# Glareshield-revA.net
KiCad netlist of a schematic drawn in EAGLE
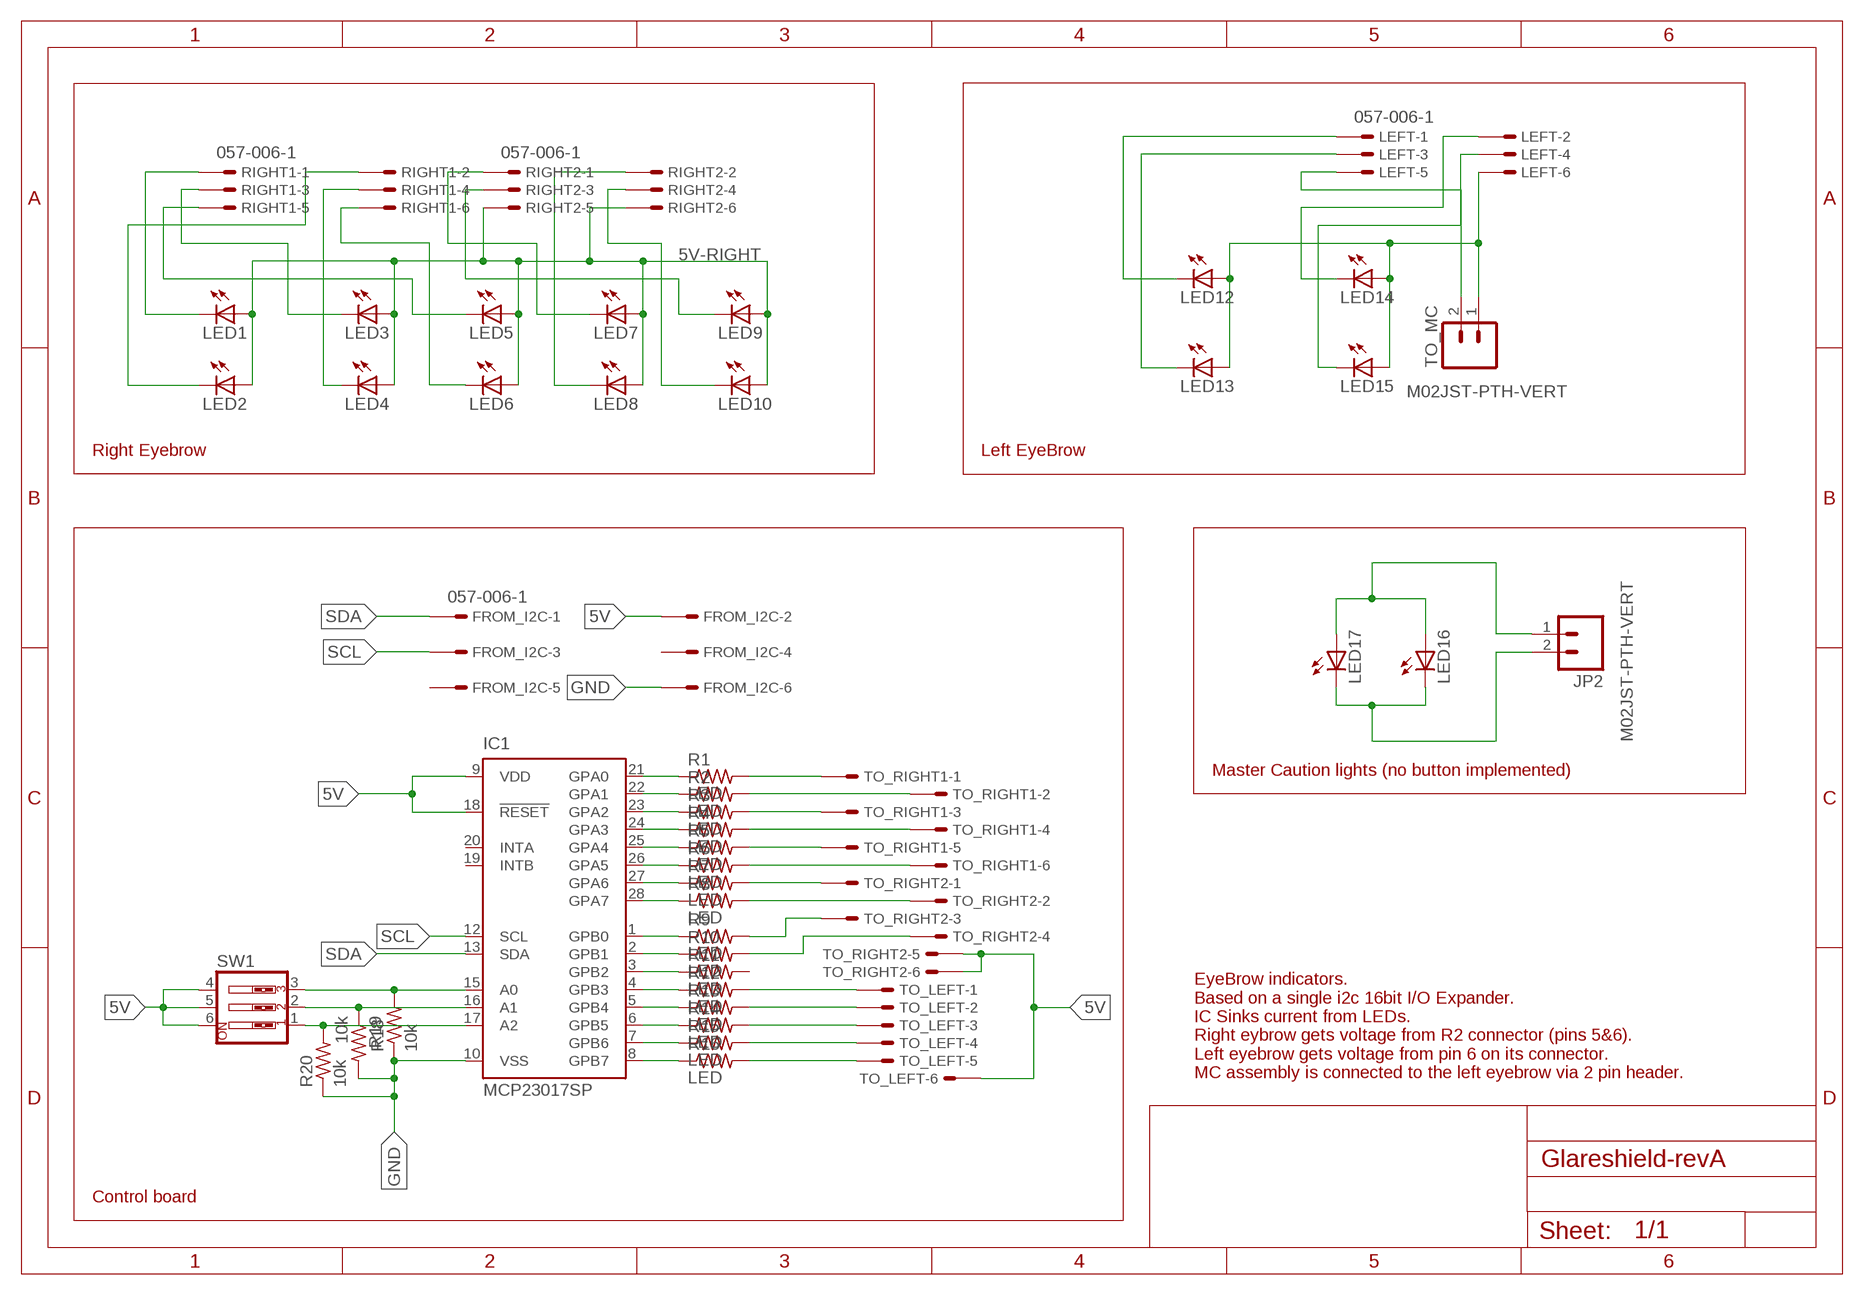
[diagram p0: schematic, sheet 1]

(export (version "E")
  (design (tool "Eeschema 10.0.6"))
  (components
    (comp (ref "FROM_I2C")
      (value "057-006-1")
      (footprint "eagle-import:057-006-1")
      (libsource (lib "eagle-import") (part "057-006-1"))
    )
    (comp (ref "IC1")
      (value "MCP23017SP")
      (footprint "eagle-import:DIL28-3")
      (fields (field (name "MF") "MICROCHIP") (field (name "MPN") "MCP23017-E/SP"))
      (libsource (lib "eagle-import") (part "MCP23017SP"))
    )
    (comp (ref "JP2")
      (value "M02JST-PTH-VERT")
      (footprint "eagle-import:JST-2-PTH-VERT")
      (libsource (lib "eagle-import") (part "M02JST-PTH-VERT"))
    )
    (comp (ref "LED1")
      (value "LED3MM")
      (footprint "eagle-import:LED3MM")
      (libsource (lib "eagle-import") (part "LED3MM"))
    )
    (comp (ref "LED2")
      (value "LED3MM")
      (footprint "eagle-import:LED3MM")
      (libsource (lib "eagle-import") (part "LED3MM"))
    )
    (comp (ref "LED3")
      (value "LED3MM")
      (footprint "eagle-import:LED3MM")
      (libsource (lib "eagle-import") (part "LED3MM"))
    )
    (comp (ref "LED4")
      (value "LED3MM")
      (footprint "eagle-import:LED3MM")
      (libsource (lib "eagle-import") (part "LED3MM"))
    )
    (comp (ref "LED5")
      (value "LED3MM")
      (footprint "eagle-import:LED3MM")
      (libsource (lib "eagle-import") (part "LED3MM"))
    )
    (comp (ref "LED6")
      (value "LED3MM")
      (footprint "eagle-import:LED3MM")
      (libsource (lib "eagle-import") (part "LED3MM"))
    )
    (comp (ref "LED7")
      (value "LED3MM")
      (footprint "eagle-import:LED3MM")
      (libsource (lib "eagle-import") (part "LED3MM"))
    )
    (comp (ref "LED8")
      (value "LED3MM")
      (footprint "eagle-import:LED3MM")
      (libsource (lib "eagle-import") (part "LED3MM"))
    )
    (comp (ref "LED9")
      (value "LED3MM")
      (footprint "eagle-import:LED3MM")
      (libsource (lib "eagle-import") (part "LED3MM"))
    )
    (comp (ref "LED10")
      (value "LED3MM")
      (footprint "eagle-import:LED3MM")
      (libsource (lib "eagle-import") (part "LED3MM"))
    )
    (comp (ref "LED12")
      (value "LED3MM")
      (footprint "eagle-import:LED3MM")
      (libsource (lib "eagle-import") (part "LED3MM"))
    )
    (comp (ref "LED13")
      (value "LED3MM")
      (footprint "eagle-import:LED3MM")
      (libsource (lib "eagle-import") (part "LED3MM"))
    )
    (comp (ref "LED14")
      (value "LED3MM")
      (footprint "eagle-import:LED3MM")
      (libsource (lib "eagle-import") (part "LED3MM"))
    )
    (comp (ref "LED15")
      (value "LED3MM")
      (footprint "eagle-import:LED3MM")
      (libsource (lib "eagle-import") (part "LED3MM"))
    )
    (comp (ref "LED16")
      (value "LED3MM")
      (footprint "eagle-import:LED3MM")
      (libsource (lib "eagle-import") (part "LED3MM"))
    )
    (comp (ref "LED17")
      (value "LED3MM")
      (footprint "eagle-import:LED3MM")
      (libsource (lib "eagle-import") (part "LED3MM"))
    )
    (comp (ref "LEFT")
      (value "057-006-1")
      (footprint "eagle-import:057-006-1")
      (libsource (lib "eagle-import") (part "057-006-1"))
    )
    (comp (ref "R1")
      (value "LED")
      (footprint "eagle-import:0204_7")
      (libsource (lib "eagle-import") (part "R-US_0204/7"))
    )
    (comp (ref "R2")
      (value "LED")
      (footprint "eagle-import:0204_7")
      (libsource (lib "eagle-import") (part "R-US_0204/7"))
    )
    (comp (ref "R3")
      (value "LED")
      (footprint "eagle-import:0204_7")
      (libsource (lib "eagle-import") (part "R-US_0204/7"))
    )
    (comp (ref "R4")
      (value "LED")
      (footprint "eagle-import:0204_7")
      (libsource (lib "eagle-import") (part "R-US_0204/7"))
    )
    (comp (ref "R5")
      (value "LED")
      (footprint "eagle-import:0204_7")
      (libsource (lib "eagle-import") (part "R-US_0204/7"))
    )
    (comp (ref "R6")
      (value "LED")
      (footprint "eagle-import:0204_7")
      (libsource (lib "eagle-import") (part "R-US_0204/7"))
    )
    (comp (ref "R7")
      (value "LED")
      (footprint "eagle-import:0204_7")
      (libsource (lib "eagle-import") (part "R-US_0204/7"))
    )
    (comp (ref "R8")
      (value "LED")
      (footprint "eagle-import:0204_7")
      (libsource (lib "eagle-import") (part "R-US_0204/7"))
    )
    (comp (ref "R9")
      (value "LED")
      (footprint "eagle-import:0204_7")
      (libsource (lib "eagle-import") (part "R-US_0204/7"))
    )
    (comp (ref "R10")
      (value "LED")
      (footprint "eagle-import:0204_7")
      (libsource (lib "eagle-import") (part "R-US_0204/7"))
    )
    (comp (ref "R11")
      (value "LED")
      (footprint "eagle-import:0204_7")
      (libsource (lib "eagle-import") (part "R-US_0204/7"))
    )
    (comp (ref "R12")
      (value "LED")
      (footprint "eagle-import:0204_7")
      (libsource (lib "eagle-import") (part "R-US_0204/7"))
    )
    (comp (ref "R13")
      (value "LED")
      (footprint "eagle-import:0204_7")
      (libsource (lib "eagle-import") (part "R-US_0204/7"))
    )
    (comp (ref "R14")
      (value "LED")
      (footprint "eagle-import:0204_7")
      (libsource (lib "eagle-import") (part "R-US_0204/7"))
    )
    (comp (ref "R15")
      (value "LED")
      (footprint "eagle-import:0204_7")
      (libsource (lib "eagle-import") (part "R-US_0204/7"))
    )
    (comp (ref "R16")
      (value "LED")
      (footprint "eagle-import:0204_7")
      (libsource (lib "eagle-import") (part "R-US_0204/7"))
    )
    (comp (ref "R18")
      (value "10k")
      (footprint "eagle-import:0204_7")
      (libsource (lib "eagle-import") (part "R-US_0204/7"))
    )
    (comp (ref "R19")
      (value "10k")
      (footprint "eagle-import:0204_7")
      (libsource (lib "eagle-import") (part "R-US_0204/7"))
    )
    (comp (ref "R20")
      (value "10k")
      (footprint "eagle-import:0204_7")
      (libsource (lib "eagle-import") (part "R-US_0204/7"))
    )
    (comp (ref "RIGHT1")
      (value "057-006-1")
      (footprint "eagle-import:057-006-1")
      (libsource (lib "eagle-import") (part "057-006-1"))
    )
    (comp (ref "RIGHT2")
      (value "057-006-1")
      (footprint "eagle-import:057-006-1")
      (libsource (lib "eagle-import") (part "057-006-1"))
    )
    (comp (ref "SW1")
      (value "SW_DIP-3")
      (footprint "eagle-import:EDG-03")
      (libsource (lib "eagle-import") (part "SW_DIP-3"))
    )
    (comp (ref "TO_LEFT")
      (value "057-006-1")
      (footprint "eagle-import:057-006-1")
      (libsource (lib "eagle-import") (part "057-006-1"))
    )
    (comp (ref "TO_MC")
      (value "M02JST-PTH-VERT")
      (footprint "eagle-import:JST-2-PTH-VERT")
      (libsource (lib "eagle-import") (part "M02JST-PTH-VERT"))
    )
    (comp (ref "TO_RIGHT1")
      (value "057-006-1")
      (footprint "eagle-import:057-006-1")
      (libsource (lib "eagle-import") (part "057-006-1"))
    )
    (comp (ref "TO_RIGHT2")
      (value "057-006-1")
      (footprint "eagle-import:057-006-1")
      (libsource (lib "eagle-import") (part "057-006-1"))
    )
  )
  (nets
    (net (code "1") (name "/5V-RIGHT") (class "Default")
      (node (ref "LED1") (pin "A") (pinfunction "A_A") (pintype "passive"))
      (node (ref "LED10") (pin "A") (pinfunction "A_A") (pintype "passive"))
      (node (ref "LED2") (pin "A") (pinfunction "A_A") (pintype "passive"))
      (node (ref "LED3") (pin "A") (pinfunction "A_A") (pintype "passive"))
      (node (ref "LED4") (pin "A") (pinfunction "A_A") (pintype "passive"))
      (node (ref "LED5") (pin "A") (pinfunction "A_A") (pintype "passive"))
      (node (ref "LED6") (pin "A") (pinfunction "A_A") (pintype "passive"))
      (node (ref "LED7") (pin "A") (pinfunction "A_A") (pintype "passive"))
      (node (ref "LED8") (pin "A") (pinfunction "A_A") (pintype "passive"))
      (node (ref "LED9") (pin "A") (pinfunction "A_A") (pintype "passive"))
      (node (ref "RIGHT2") (pin "5") (pinfunction "S_5") (pintype "passive"))
      (node (ref "RIGHT2") (pin "6") (pinfunction "S_6") (pintype "passive"))
    )
    (net (code "2") (name "5V") (class "Default")
      (node (ref "FROM_I2C") (pin "2") (pinfunction "S_2") (pintype "passive"))
      (node (ref "IC1") (pin "18") (pinfunction "~{RESET}_18") (pintype "input"))
      (node (ref "IC1") (pin "9") (pinfunction "VDD_9") (pintype "power_in"))
      (node (ref "SW1") (pin "4") (pinfunction "4_4") (pintype "passive"))
      (node (ref "SW1") (pin "5") (pinfunction "5_5") (pintype "passive"))
      (node (ref "SW1") (pin "6") (pinfunction "6_6") (pintype "passive"))
      (node (ref "TO_LEFT") (pin "6") (pinfunction "S_6") (pintype "passive"))
      (node (ref "TO_RIGHT2") (pin "5") (pinfunction "S_5") (pintype "passive"))
      (node (ref "TO_RIGHT2") (pin "6") (pinfunction "S_6") (pintype "passive"))
    )
    (net (code "3") (name "GND") (class "Default")
      (node (ref "FROM_I2C") (pin "6") (pinfunction "S_6") (pintype "passive"))
      (node (ref "IC1") (pin "10") (pinfunction "VSS_10") (pintype "power_in"))
      (node (ref "R18") (pin "1") (pinfunction "1_1") (pintype "passive"))
      (node (ref "R19") (pin "2") (pinfunction "2_2") (pintype "passive"))
      (node (ref "R20") (pin "1") (pinfunction "1_1") (pintype "passive"))
    )
    (net (code "4") (name "Net-(IC1-A0)") (class "Default")
      (node (ref "IC1") (pin "15") (pinfunction "A0_15") (pintype "input"))
      (node (ref "R18") (pin "2") (pinfunction "2_2") (pintype "passive"))
      (node (ref "SW1") (pin "3") (pinfunction "3_3") (pintype "passive"))
    )
    (net (code "5") (name "Net-(IC1-A1)") (class "Default")
      (node (ref "IC1") (pin "16") (pinfunction "A1_16") (pintype "input"))
      (node (ref "R19") (pin "1") (pinfunction "1_1") (pintype "passive"))
      (node (ref "SW1") (pin "2") (pinfunction "2_2") (pintype "passive"))
    )
    (net (code "6") (name "Net-(IC1-A2)") (class "Default")
      (node (ref "IC1") (pin "17") (pinfunction "A2_17") (pintype "input"))
      (node (ref "R20") (pin "2") (pinfunction "2_2") (pintype "passive"))
      (node (ref "SW1") (pin "1") (pinfunction "1_1") (pintype "passive"))
    )
    (net (code "7") (name "Net-(IC1-GPA0)") (class "Default")
      (node (ref "IC1") (pin "21") (pinfunction "GPA0_21") (pintype "bidirectional"))
      (node (ref "R1") (pin "1") (pinfunction "1_1") (pintype "passive"))
    )
    (net (code "8") (name "Net-(IC1-GPA1)") (class "Default")
      (node (ref "IC1") (pin "22") (pinfunction "GPA1_22") (pintype "bidirectional"))
      (node (ref "R2") (pin "1") (pinfunction "1_1") (pintype "passive"))
    )
    (net (code "9") (name "Net-(IC1-GPA2)") (class "Default")
      (node (ref "IC1") (pin "23") (pinfunction "GPA2_23") (pintype "bidirectional"))
      (node (ref "R3") (pin "1") (pinfunction "1_1") (pintype "passive"))
    )
    (net (code "10") (name "Net-(IC1-GPA3)") (class "Default")
      (node (ref "IC1") (pin "24") (pinfunction "GPA3_24") (pintype "bidirectional"))
      (node (ref "R4") (pin "1") (pinfunction "1_1") (pintype "passive"))
    )
    (net (code "11") (name "Net-(IC1-GPA4)") (class "Default")
      (node (ref "IC1") (pin "25") (pinfunction "GPA4_25") (pintype "bidirectional"))
      (node (ref "R5") (pin "1") (pinfunction "1_1") (pintype "passive"))
    )
    (net (code "12") (name "Net-(IC1-GPA5)") (class "Default")
      (node (ref "IC1") (pin "26") (pinfunction "GPA5_26") (pintype "bidirectional"))
      (node (ref "R6") (pin "1") (pinfunction "1_1") (pintype "passive"))
    )
    (net (code "13") (name "Net-(IC1-GPA6)") (class "Default")
      (node (ref "IC1") (pin "27") (pinfunction "GPA6_27") (pintype "bidirectional"))
      (node (ref "R7") (pin "1") (pinfunction "1_1") (pintype "passive"))
    )
    (net (code "14") (name "Net-(IC1-GPA7)") (class "Default")
      (node (ref "IC1") (pin "28") (pinfunction "GPA7_28") (pintype "bidirectional"))
      (node (ref "R8") (pin "1") (pinfunction "1_1") (pintype "passive"))
    )
    (net (code "15") (name "Net-(IC1-GPB0)") (class "Default")
      (node (ref "IC1") (pin "1") (pinfunction "GPB0_1") (pintype "bidirectional"))
      (node (ref "R9") (pin "1") (pinfunction "1_1") (pintype "passive"))
    )
    (net (code "16") (name "Net-(IC1-GPB1)") (class "Default")
      (node (ref "IC1") (pin "2") (pinfunction "GPB1_2") (pintype "bidirectional"))
      (node (ref "R10") (pin "1") (pinfunction "1_1") (pintype "passive"))
    )
    (net (code "17") (name "Net-(IC1-GPB2)") (class "Default")
      (node (ref "IC1") (pin "3") (pinfunction "GPB2_3") (pintype "bidirectional"))
      (node (ref "R11") (pin "1") (pinfunction "1_1") (pintype "passive"))
    )
    (net (code "18") (name "Net-(IC1-GPB3)") (class "Default")
      (node (ref "IC1") (pin "4") (pinfunction "GPB3_4") (pintype "bidirectional"))
      (node (ref "R12") (pin "1") (pinfunction "1_1") (pintype "passive"))
    )
    (net (code "19") (name "Net-(IC1-GPB4)") (class "Default")
      (node (ref "IC1") (pin "5") (pinfunction "GPB4_5") (pintype "bidirectional"))
      (node (ref "R13") (pin "1") (pinfunction "1_1") (pintype "passive"))
    )
    (net (code "20") (name "Net-(IC1-GPB5)") (class "Default")
      (node (ref "IC1") (pin "6") (pinfunction "GPB5_6") (pintype "bidirectional"))
      (node (ref "R14") (pin "1") (pinfunction "1_1") (pintype "passive"))
    )
    (net (code "21") (name "Net-(IC1-GPB6)") (class "Default")
      (node (ref "IC1") (pin "7") (pinfunction "GPB6_7") (pintype "bidirectional"))
      (node (ref "R15") (pin "1") (pinfunction "1_1") (pintype "passive"))
    )
    (net (code "22") (name "Net-(IC1-GPB7)") (class "Default")
      (node (ref "IC1") (pin "8") (pinfunction "GPB7_8") (pintype "bidirectional"))
      (node (ref "R16") (pin "1") (pinfunction "1_1") (pintype "passive"))
    )
    (net (code "23") (name "Net-(JP2-Pad1)") (class "Default")
      (node (ref "JP2") (pin "1") (pinfunction "1_1") (pintype "passive"))
      (node (ref "LED16") (pin "A") (pinfunction "A_A") (pintype "passive"))
      (node (ref "LED17") (pin "A") (pinfunction "A_A") (pintype "passive"))
    )
    (net (code "24") (name "Net-(LED1-C)") (class "Default")
      (node (ref "LED1") (pin "K") (pinfunction "C_K") (pintype "passive"))
      (node (ref "RIGHT1") (pin "1") (pinfunction "S_1") (pintype "passive"))
    )
    (net (code "25") (name "Net-(LED2-C)") (class "Default")
      (node (ref "LED2") (pin "K") (pinfunction "C_K") (pintype "passive"))
      (node (ref "RIGHT1") (pin "2") (pinfunction "S_2") (pintype "passive"))
    )
    (net (code "26") (name "Net-(LED3-C)") (class "Default")
      (node (ref "LED3") (pin "K") (pinfunction "C_K") (pintype "passive"))
      (node (ref "RIGHT1") (pin "3") (pinfunction "S_3") (pintype "passive"))
    )
    (net (code "27") (name "Net-(LED4-C)") (class "Default")
      (node (ref "LED4") (pin "K") (pinfunction "C_K") (pintype "passive"))
      (node (ref "RIGHT1") (pin "4") (pinfunction "S_4") (pintype "passive"))
    )
    (net (code "28") (name "Net-(LED5-C)") (class "Default")
      (node (ref "LED5") (pin "K") (pinfunction "C_K") (pintype "passive"))
      (node (ref "RIGHT1") (pin "5") (pinfunction "S_5") (pintype "passive"))
    )
    (net (code "29") (name "Net-(LED6-C)") (class "Default")
      (node (ref "LED6") (pin "K") (pinfunction "C_K") (pintype "passive"))
      (node (ref "RIGHT1") (pin "6") (pinfunction "S_6") (pintype "passive"))
    )
    (net (code "30") (name "Net-(LED7-C)") (class "Default")
      (node (ref "LED7") (pin "K") (pinfunction "C_K") (pintype "passive"))
      (node (ref "RIGHT2") (pin "1") (pinfunction "S_1") (pintype "passive"))
    )
    (net (code "31") (name "Net-(LED8-C)") (class "Default")
      (node (ref "LED8") (pin "K") (pinfunction "C_K") (pintype "passive"))
      (node (ref "RIGHT2") (pin "2") (pinfunction "S_2") (pintype "passive"))
    )
    (net (code "32") (name "Net-(LED9-C)") (class "Default")
      (node (ref "LED9") (pin "K") (pinfunction "C_K") (pintype "passive"))
      (node (ref "RIGHT2") (pin "3") (pinfunction "S_3") (pintype "passive"))
    )
    (net (code "33") (name "Net-(LED10-C)") (class "Default")
      (node (ref "LED10") (pin "K") (pinfunction "C_K") (pintype "passive"))
      (node (ref "RIGHT2") (pin "4") (pinfunction "S_4") (pintype "passive"))
    )
    (net (code "34") (name "Net-(LED12-C)") (class "Default")
      (node (ref "LED12") (pin "K") (pinfunction "C_K") (pintype "passive"))
      (node (ref "LEFT") (pin "1") (pinfunction "S_1") (pintype "passive"))
    )
    (net (code "35") (name "Net-(LED13-C)") (class "Default")
      (node (ref "LED13") (pin "K") (pinfunction "C_K") (pintype "passive"))
      (node (ref "LEFT") (pin "3") (pinfunction "S_3") (pintype "passive"))
    )
    (net (code "36") (name "Net-(LED14-C)") (class "Default")
      (node (ref "LED14") (pin "K") (pinfunction "C_K") (pintype "passive"))
      (node (ref "LEFT") (pin "2") (pinfunction "S_2") (pintype "passive"))
    )
    (net (code "37") (name "Net-(LED15-C)") (class "Default")
      (node (ref "LED15") (pin "K") (pinfunction "C_K") (pintype "passive"))
      (node (ref "LEFT") (pin "4") (pinfunction "S_4") (pintype "passive"))
    )
    (net (code "38") (name "Net-(LED16-C)") (class "Default")
      (node (ref "JP2") (pin "2") (pinfunction "2_2") (pintype "passive"))
      (node (ref "LED16") (pin "K") (pinfunction "C_K") (pintype "passive"))
      (node (ref "LED17") (pin "K") (pinfunction "C_K") (pintype "passive"))
    )
    (net (code "39") (name "Net-(LEFTE-S)") (class "Default")
      (node (ref "LEFT") (pin "5") (pinfunction "S_5") (pintype "passive"))
      (node (ref "TO_MC") (pin "2") (pinfunction "2_2") (pintype "passive"))
    )
    (net (code "40") (name "Net-(LEFTF-S)") (class "Default")
      (node (ref "LED12") (pin "A") (pinfunction "A_A") (pintype "passive"))
      (node (ref "LED13") (pin "A") (pinfunction "A_A") (pintype "passive"))
      (node (ref "LED14") (pin "A") (pinfunction "A_A") (pintype "passive"))
      (node (ref "LED15") (pin "A") (pinfunction "A_A") (pintype "passive"))
      (node (ref "LEFT") (pin "6") (pinfunction "S_6") (pintype "passive"))
      (node (ref "TO_MC") (pin "1") (pinfunction "1_1") (pintype "passive"))
    )
    (net (code "41") (name "Net-(TO_LEFTA-S)") (class "Default")
      (node (ref "R12") (pin "2") (pinfunction "2_2") (pintype "passive"))
      (node (ref "TO_LEFT") (pin "1") (pinfunction "S_1") (pintype "passive"))
    )
    (net (code "42") (name "Net-(TO_LEFTB-S)") (class "Default")
      (node (ref "R13") (pin "2") (pinfunction "2_2") (pintype "passive"))
      (node (ref "TO_LEFT") (pin "2") (pinfunction "S_2") (pintype "passive"))
    )
    (net (code "43") (name "Net-(TO_LEFTC-S)") (class "Default")
      (node (ref "R14") (pin "2") (pinfunction "2_2") (pintype "passive"))
      (node (ref "TO_LEFT") (pin "3") (pinfunction "S_3") (pintype "passive"))
    )
    (net (code "44") (name "Net-(TO_LEFTD-S)") (class "Default")
      (node (ref "R15") (pin "2") (pinfunction "2_2") (pintype "passive"))
      (node (ref "TO_LEFT") (pin "4") (pinfunction "S_4") (pintype "passive"))
    )
    (net (code "45") (name "Net-(TO_LEFTE-S)") (class "Default")
      (node (ref "R16") (pin "2") (pinfunction "2_2") (pintype "passive"))
      (node (ref "TO_LEFT") (pin "5") (pinfunction "S_5") (pintype "passive"))
    )
    (net (code "46") (name "Net-(TO_RIGHT1A-S)") (class "Default")
      (node (ref "R1") (pin "2") (pinfunction "2_2") (pintype "passive"))
      (node (ref "TO_RIGHT1") (pin "1") (pinfunction "S_1") (pintype "passive"))
    )
    (net (code "47") (name "Net-(TO_RIGHT1B-S)") (class "Default")
      (node (ref "R2") (pin "2") (pinfunction "2_2") (pintype "passive"))
      (node (ref "TO_RIGHT1") (pin "2") (pinfunction "S_2") (pintype "passive"))
    )
    (net (code "48") (name "Net-(TO_RIGHT1C-S)") (class "Default")
      (node (ref "R3") (pin "2") (pinfunction "2_2") (pintype "passive"))
      (node (ref "TO_RIGHT1") (pin "3") (pinfunction "S_3") (pintype "passive"))
    )
    (net (code "49") (name "Net-(TO_RIGHT1D-S)") (class "Default")
      (node (ref "R4") (pin "2") (pinfunction "2_2") (pintype "passive"))
      (node (ref "TO_RIGHT1") (pin "4") (pinfunction "S_4") (pintype "passive"))
    )
    (net (code "50") (name "Net-(TO_RIGHT1E-S)") (class "Default")
      (node (ref "R5") (pin "2") (pinfunction "2_2") (pintype "passive"))
      (node (ref "TO_RIGHT1") (pin "5") (pinfunction "S_5") (pintype "passive"))
    )
    (net (code "51") (name "Net-(TO_RIGHT1F-S)") (class "Default")
      (node (ref "R6") (pin "2") (pinfunction "2_2") (pintype "passive"))
      (node (ref "TO_RIGHT1") (pin "6") (pinfunction "S_6") (pintype "passive"))
    )
    (net (code "52") (name "Net-(TO_RIGHT2A-S)") (class "Default")
      (node (ref "R7") (pin "2") (pinfunction "2_2") (pintype "passive"))
      (node (ref "TO_RIGHT2") (pin "1") (pinfunction "S_1") (pintype "passive"))
    )
    (net (code "53") (name "Net-(TO_RIGHT2B-S)") (class "Default")
      (node (ref "R8") (pin "2") (pinfunction "2_2") (pintype "passive"))
      (node (ref "TO_RIGHT2") (pin "2") (pinfunction "S_2") (pintype "passive"))
    )
    (net (code "54") (name "Net-(TO_RIGHT2C-S)") (class "Default")
      (node (ref "R9") (pin "2") (pinfunction "2_2") (pintype "passive"))
      (node (ref "TO_RIGHT2") (pin "3") (pinfunction "S_3") (pintype "passive"))
    )
    (net (code "55") (name "Net-(TO_RIGHT2D-S)") (class "Default")
      (node (ref "R10") (pin "2") (pinfunction "2_2") (pintype "passive"))
      (node (ref "TO_RIGHT2") (pin "4") (pinfunction "S_4") (pintype "passive"))
    )
    (net (code "56") (name "SCL") (class "Default")
      (node (ref "FROM_I2C") (pin "3") (pinfunction "S_3") (pintype "passive"))
      (node (ref "IC1") (pin "12") (pinfunction "SCL_12") (pintype "input"))
    )
    (net (code "57") (name "SDA") (class "Default")
      (node (ref "FROM_I2C") (pin "1") (pinfunction "S_1") (pintype "passive"))
      (node (ref "IC1") (pin "13") (pinfunction "SDA_13") (pintype "bidirectional"))
    )
    (net (code "58") (name "unconnected-(FROM_I2CD-S-Pad4)") (class "Default")
      (node (ref "FROM_I2C") (pin "4") (pinfunction "S_4") (pintype "passive"))
    )
    (net (code "59") (name "unconnected-(FROM_I2CE-S-Pad5)") (class "Default")
      (node (ref "FROM_I2C") (pin "5") (pinfunction "S_5") (pintype "passive"))
    )
    (net (code "60") (name "unconnected-(IC1-INTA-Pad20)") (class "Default")
      (node (ref "IC1") (pin "20") (pinfunction "INTA_20") (pintype "output"))
    )
    (net (code "61") (name "unconnected-(IC1-INTB-Pad19)") (class "Default")
      (node (ref "IC1") (pin "19") (pinfunction "INTB_19") (pintype "output"))
    )
    (net (code "62") (name "unconnected-(R11-Pad2)") (class "Default")
      (node (ref "R11") (pin "2") (pinfunction "2_2") (pintype "passive"))
    )
  )
)
